# 02_-STM32F373BluePill.net
KiCad netlist of a schematic drawn in Altium Designer
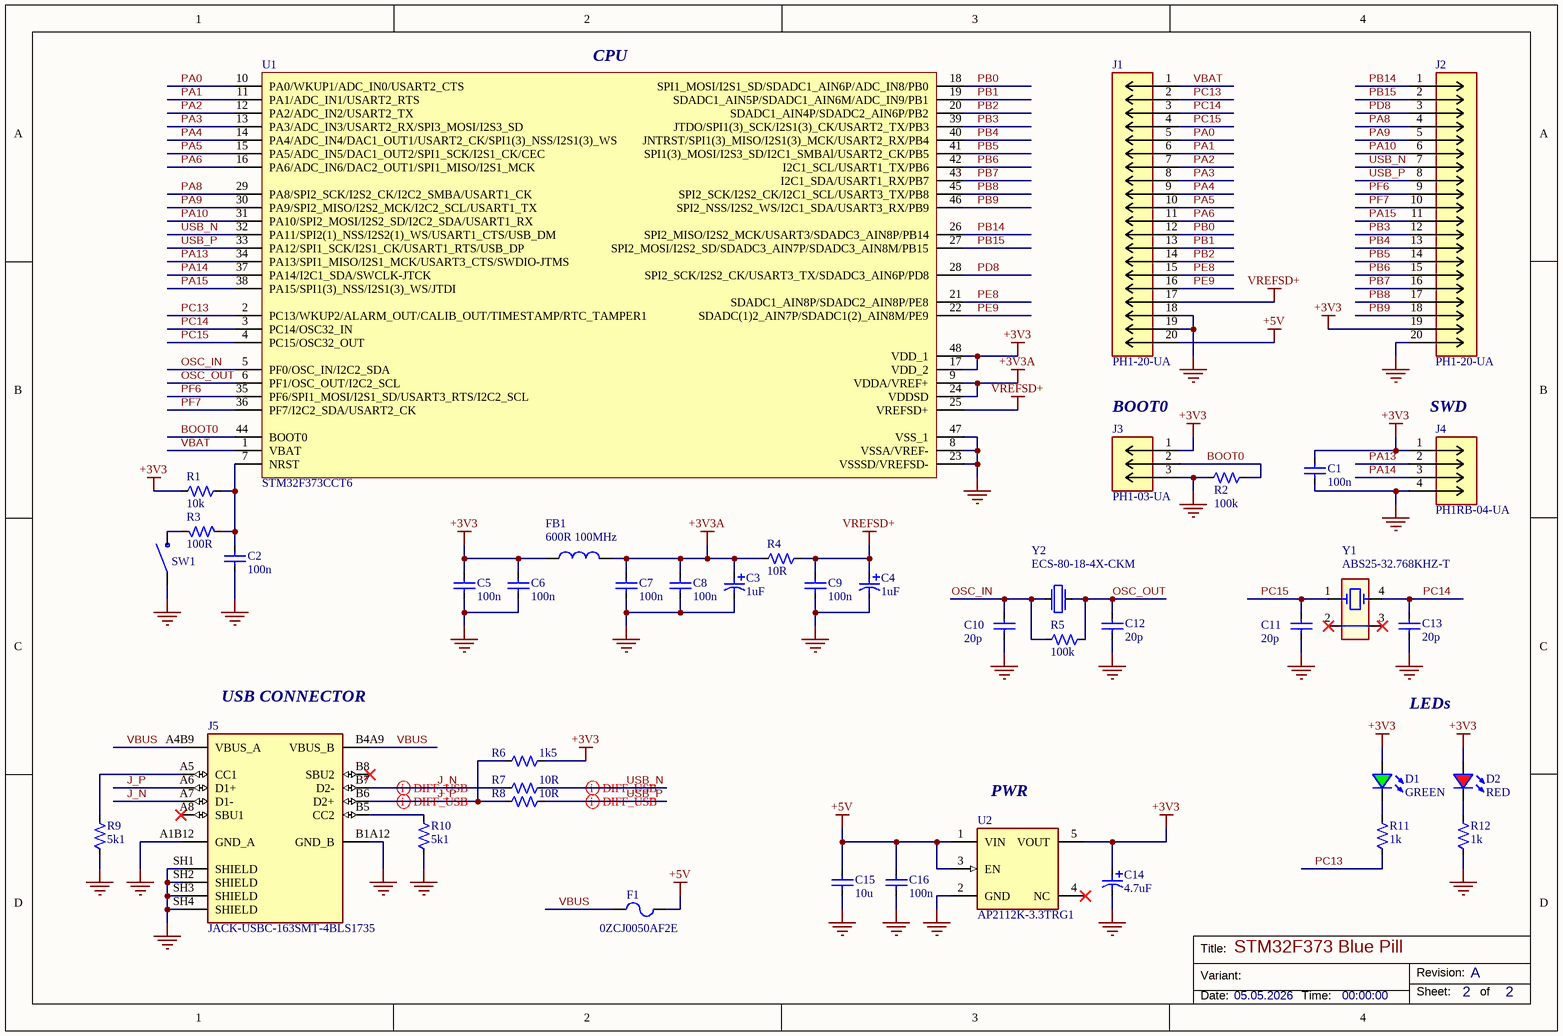
[diagram p0: [02]-STM32F373BluePill.SchDoc]

(export (version "E")
  (design (tool "Eeschema 10.0.6"))
  (components
    (comp (ref "C1")
      (value "100n")
      (footprint "CAPC0603(1608Metric)L")
      (description "0.1 µF ±10% 50V Ceramic Capacitor X7R 0603 (1608 Metric)")
      (fields (field (name "TOLERANCE") "10%"))
      (libsource (lib "STM32F373BluePill") (part "CAPC_GCM188R71H104KA57J"))
    )
    (comp (ref "C2")
      (value "100n")
      (footprint "CAPC0603(1608Metric)L")
      (description "0.1 µF ±10% 50V Ceramic Capacitor X7R 0603 (1608 Metric)")
      (fields (field (name "TOLERANCE") "10%"))
      (libsource (lib "STM32F373BluePill") (part "CAPC_GCM188R71H104KA57J"))
    )
    (comp (ref "C3")
      (value "1uF")
      (footprint "CAPMP3216X180N")
      (description "1 µF Molded Tantalum Capacitors 20 V 1206 (3216 Metric) 9Ohm")
      (fields (field (name "TOLERANCE") "10%") (field (name "VOLTAGE") "20V"))
      (libsource (lib "STM32F373BluePill") (part "CAP_T491A105K020AT"))
    )
    (comp (ref "C4")
      (value "1uF")
      (footprint "CAPMP3216X180N")
      (description "1 µF Molded Tantalum Capacitors 20 V 1206 (3216 Metric) 9Ohm")
      (fields (field (name "TOLERANCE") "10%") (field (name "VOLTAGE") "20V"))
      (libsource (lib "STM32F373BluePill") (part "CAP_T491A105K020AT"))
    )
    (comp (ref "C5")
      (value "100n")
      (footprint "CAPC0603(1608Metric)L")
      (description "0.1 µF ±10% 50V Ceramic Capacitor X7R 0603 (1608 Metric)")
      (fields (field (name "TOLERANCE") "10%"))
      (libsource (lib "STM32F373BluePill") (part "CAPC_GCM188R71H104KA57J"))
    )
    (comp (ref "C6")
      (value "100n")
      (footprint "CAPC0603(1608Metric)L")
      (description "0.1 µF ±10% 50V Ceramic Capacitor X7R 0603 (1608 Metric)")
      (fields (field (name "TOLERANCE") "10%"))
      (libsource (lib "STM32F373BluePill") (part "CAPC_GCM188R71H104KA57J"))
    )
    (comp (ref "C7")
      (value "100n")
      (footprint "CAPC0603(1608Metric)L")
      (description "0.1 µF ±10% 50V Ceramic Capacitor X7R 0603 (1608 Metric)")
      (fields (field (name "TOLERANCE") "10%"))
      (libsource (lib "STM32F373BluePill") (part "CAPC_GCM188R71H104KA57J"))
    )
    (comp (ref "C8")
      (value "100n")
      (footprint "CAPC0603(1608Metric)L")
      (description "0.1 µF ±10% 50V Ceramic Capacitor X7R 0603 (1608 Metric)")
      (fields (field (name "TOLERANCE") "10%"))
      (libsource (lib "STM32F373BluePill") (part "CAPC_GCM188R71H104KA57J"))
    )
    (comp (ref "C9")
      (value "100n")
      (footprint "CAPC0603(1608Metric)L")
      (description "0.1 µF ±10% 50V Ceramic Capacitor X7R 0603 (1608 Metric)")
      (fields (field (name "TOLERANCE") "10%"))
      (libsource (lib "STM32F373BluePill") (part "CAPC_GCM188R71H104KA57J"))
    )
    (comp (ref "C10")
      (value "20p")
      (footprint "CAPC0603(1608Metric)L")
      (description "20pF 100V C0G ±5% 0603 Multilayer Ceramic Capacitors MLCC - SMD/SMT ROHS")
      (fields (field (name "TOLERANCE") "5%"))
      (libsource (lib "STM32F373BluePill") (part "CAPC_GCM1885C2A200JA16D"))
    )
    (comp (ref "C11")
      (value "20p")
      (footprint "CAPC0603(1608Metric)L")
      (description "20pF 100V C0G ±5% 0603 Multilayer Ceramic Capacitors MLCC - SMD/SMT ROHS")
      (fields (field (name "TOLERANCE") "5%"))
      (libsource (lib "STM32F373BluePill") (part "CAPC_GCM1885C2A200JA16D"))
    )
    (comp (ref "C12")
      (value "20p")
      (footprint "CAPC0603(1608Metric)L")
      (description "20pF 100V C0G ±5% 0603 Multilayer Ceramic Capacitors MLCC - SMD/SMT ROHS")
      (fields (field (name "TOLERANCE") "5%"))
      (libsource (lib "STM32F373BluePill") (part "CAPC_GCM1885C2A200JA16D"))
    )
    (comp (ref "C13")
      (value "20p")
      (footprint "CAPC0603(1608Metric)L")
      (description "20pF 100V C0G ±5% 0603 Multilayer Ceramic Capacitors MLCC - SMD/SMT ROHS")
      (fields (field (name "TOLERANCE") "5%"))
      (libsource (lib "STM32F373BluePill") (part "CAPC_GCM1885C2A200JA16D"))
    )
    (comp (ref "C14")
      (value "4.7uF")
      (footprint "CAPMP3216X180N")
      (description "4.7 µF Molded Tantalum Capacitors 25 V 1206 (3216 Metric) 6Ohm")
      (fields (field (name "TOLERANCE") "10%"))
      (libsource (lib "STM32F373BluePill") (part "CAP_T491A475K025AT"))
    )
    (comp (ref "C15")
      (value "10u")
      (footprint "CAPC0603(1608Metric)L")
      (description "10 µF ±20% 16V Ceramic Capacitor X6S 0603 (1608 Metric)")
      (fields (field (name "TOLERANCE") "20%") (field (name "VOLTAGE") "16V"))
      (libsource (lib "STM32F373BluePill") (part "CAPC_GRM188C81C106MA73D"))
    )
    (comp (ref "C16")
      (value "100n")
      (footprint "CAPC0603(1608Metric)L")
      (description "0.1 µF ±10% 50V Ceramic Capacitor X7R 0603 (1608 Metric)")
      (fields (field (name "TOLERANCE") "10%"))
      (libsource (lib "STM32F373BluePill") (part "CAPC_GCM188R71H104KA57J"))
    )
    (comp (ref "D1")
      (value "GREEN")
      (footprint "WL-SMCW_0603_150060xx75003")
      (description "Led, Bright Green, 100Mcd, 572Nm Rohs Compliant: Yes")
      (libsource (lib "STM32F373BluePill") (part "LED_150060VS75003"))
    )
    (comp (ref "D2")
      (value "RED")
      (footprint "WL-SMCW_0603_150060xx75003")
      (description "LED RED CLEAR 0603 SMD")
      (libsource (lib "STM32F373BluePill") (part "LED_150060RS75003"))
    )
    (comp (ref "F1")
      (value "0ZCJ0050AF2E")
      (footprint "0ZCJ_BEL")
      (description "Resettable Fuse, PPTC, 1206 (3216 Metric), 0ZCJ Series, 24 VDC, 500 mA, 1 A, 0.1 s")
      (libsource (lib "STLinkV2_1") (part "0ZCJ0050AF2E"))
    )
    (comp (ref "FB1")
      (value "600R 100MHz")
      (footprint "BEADC1608X95N")
      (description "600 Ohms @ 100 MHz 1 Ferrite Bead 0603 (1608 Metric) 500mA 380mOhm")
      (fields (field (name "TOLERANCE") "25%"))
      (libsource (lib "STM32F373BluePill") (part "BLM18AG601SN1D"))
    )
    (comp (ref "J1")
      (value "PH1-20-UA")
      (footprint "CONN_PH1-20-UA_ADM")
      (description "Conn Unshrouded Header HDR 10 POS 2.54mm Solder RA Side Entry Thru-Hole Bag")
      (libsource (lib "STM32F373BluePill") (part "CON_PH1-20-UA"))
    )
    (comp (ref "J2")
      (value "PH1-20-UA")
      (footprint "CONN_PH1-20-UA_ADM")
      (description "Conn Unshrouded Header HDR 10 POS 2.54mm Solder RA Side Entry Thru-Hole Bag")
      (libsource (lib "STM32F373BluePill") (part "CON_PH1-20-UA"))
    )
    (comp (ref "J3")
      (value "PH1-03-UA")
      (footprint "CONN_PH1-03-UA")
      (description "Conn Unshrouded Header HDR 3 POS 2.54mm Solder ST Top Entry Thru-Hole Bag")
      (libsource (lib "STM32F373BluePill") (part "CON_PH1-03-UA"))
    )
    (comp (ref "J4")
      (value "PH1RB-04-UA")
      (footprint "CONN_PH1RB-04-UA")
      (description "PH1RB ROHS3Compliant COMMERCIAL UL CSA Connector Header 20mOhm -40C~105C 3A 250VAC")
      (libsource (lib "STM32F373BluePill") (part "CON_PH1RB-04-UA"))
    )
    (comp (ref "J5")
      (value "JACK-USBC-163SMT-4BLS1735")
      (footprint "JACK-USBC-163SMT-4BLS1735")
      (description "Usb Type C Jack IPX7 SMT")
      (libsource (lib "STLinkV2_1") (part "JACK-USBC-163SMT-4BLS1735"))
    )
    (comp (ref "R1")
      (value "10k")
      (footprint "RESC0603(1608Metric)L")
      (fields (field (name "TOLERANCE") "1%"))
      (libsource (lib "STM32F373BluePill") (part "RESC_AC0603FR-0710KL"))
    )
    (comp (ref "R2")
      (value "100k")
      (footprint "RESC0603(1608Metric)L")
      (description "100 kOhms ±0.5% 0.1W, 1/10W Chip Resistor 0603 (1608 Metric) Moisture Resistant Thick Film")
      (fields (field (name "TOLERANCE") "0.5%"))
      (libsource (lib "STM32F373BluePill") (part "RESC_RC0603DR-07100KL"))
    )
    (comp (ref "R3")
      (value "100R")
      (footprint "RESC0603(1608Metric)L")
      (description "100 Ohms ±1% 0.1W, 1/10W Chip Resistor 0603 (1608 Metric) Moisture Resistant Thick Film")
      (fields (field (name "TOLERANCE") "1%"))
      (libsource (lib "STM32F373BluePill") (part "RESC_RC0603FR-10100RL"))
    )
    (comp (ref "R4")
      (value "10R")
      (footprint "RESC0603(1608Metric)L")
      (description "Res Thick Film 0603 10 Ohm 1% 0.1W(1/10W) ±200ppm/C Pad SMD T/R")
      (fields (field (name "TOLERANCE") "1%"))
      (libsource (lib "STM32F373BluePill") (part "RESC_RC0603FR-0710RL"))
    )
    (comp (ref "R5")
      (value "100k")
      (footprint "RESC0603(1608Metric)L")
      (description "100 kOhms ±0.5% 0.1W, 1/10W Chip Resistor 0603 (1608 Metric) Moisture Resistant Thick Film")
      (fields (field (name "TOLERANCE") "0.5%"))
      (libsource (lib "STM32F373BluePill") (part "RESC_RC0603DR-07100KL"))
    )
    (comp (ref "R6")
      (value "1k5")
      (footprint "RESC0603(1608Metric)L")
      (fields (field (name "TOLERANCE") "1%"))
      (libsource (lib "STM32F373BluePill") (part "RESC_AC0603FR-071K5L"))
    )
    (comp (ref "R7")
      (value "10R")
      (footprint "RESC0603(1608Metric)L")
      (description "Res Thick Film 0603 10 Ohm 1% 0.1W(1/10W) ±200ppm/C Pad SMD T/R")
      (fields (field (name "TOLERANCE") "1%"))
      (libsource (lib "STM32F373BluePill") (part "RESC_RC0603FR-0710RL"))
    )
    (comp (ref "R8")
      (value "10R")
      (footprint "RESC0603(1608Metric)L")
      (description "Res Thick Film 0603 10 Ohm 1% 0.1W(1/10W) ±200ppm/C Pad SMD T/R")
      (fields (field (name "TOLERANCE") "1%"))
      (libsource (lib "STM32F373BluePill") (part "RESC_RC0603FR-0710RL"))
    )
    (comp (ref "R9")
      (value "5k1")
      (footprint "RESC0603(1608Metric)L")
      (description "5.1 kOhms ±1% 0.1W, 1/10W Chip Resistor 0603 (1608 Metric) Moisture Resistant Thick Film")
      (fields (field (name "TOLERANCE") "1%"))
      (libsource (lib "STM32F373BluePill") (part "RESC_RC0603FR-075K1L"))
    )
    (comp (ref "R10")
      (value "5k1")
      (footprint "RESC0603(1608Metric)L")
      (description "5.1 kOhms ±1% 0.1W, 1/10W Chip Resistor 0603 (1608 Metric) Moisture Resistant Thick Film")
      (fields (field (name "TOLERANCE") "1%"))
      (libsource (lib "STM32F373BluePill") (part "RESC_RC0603FR-075K1L"))
    )
    (comp (ref "R11")
      (value "1k")
      (footprint "RESC0603(1608Metric)L")
      (description "1 kOhms ±1% 0.1W, 1/10W Chip Resistor 0603 (1608 Metric) Moisture Resistant Thick Film")
      (fields (field (name "TOLERANCE") "1%"))
      (libsource (lib "STM32F373BluePill") (part "RESC_RC0603FR-101KL"))
    )
    (comp (ref "R12")
      (value "1k")
      (footprint "RESC0603(1608Metric)L")
      (description "1 kOhms ±1% 0.1W, 1/10W Chip Resistor 0603 (1608 Metric) Moisture Resistant Thick Film")
      (fields (field (name "TOLERANCE") "1%"))
      (libsource (lib "STM32F373BluePill") (part "RESC_RC0603FR-101KL"))
    )
    (comp (ref "SW1")
      (value "TS09-63-25-R-260-SMT-TR")
      (footprint "SW_TS09-63-25-R-260-SMT-TR")
      (description "Switch Tactile OFF (ON) SPST Rectangular Button Gull Wing 0.05A 12VDC 40000Cycles 2.6N SMD T/R")
      (libsource (lib "STM32F373BluePill") (part "SW_TS09-63-25-R-260-SMT-TR"))
    )
    (comp (ref "U1")
      (value "STM32F373CCT6")
      (footprint "QFP50P900X900X160-48N")
      (description "MCU, 32BIT, CORTEX-M4F, 72MHZ, LQFP-48")
      (fields (field (name "MANUFACTURER") "STMicroelectronics"))
      (libsource (lib "STM32F373BluePill") (part "IC_STM32F373CCT6"))
    )
    (comp (ref "U2")
      (value "AP2112K-3.3TRG1")
      (footprint "SOT95P285X140-5N")
      (description "AP2112 Series 0.6 A 3.3 V Fixed Output SMT LDO Linear Regulator - SOT23-5")
      (libsource (lib "STLinkV2_1") (part "AP2112K-3.3TRG1"))
    )
    (comp (ref "Y1")
      (value "ABS25-32.768KHZ-T")
      (footprint "XTAL_ABS25-32.768KHZ-6-1-T")
      (description "Crystal, Plastic Molded 32.768Khz, 12.5F, 20Ppm-40+85C, 8 X 4 X 2.5 Rohs Compliant: Yes")
      (fields (field (name "TOLERANCE") "0.002%"))
      (libsource (lib "STM32F373BluePill") (part "Y_ABS25-32.768KHZ-T"))
    )
    (comp (ref "Y2")
      (value "ECS-80-18-4X-CKM")
      (footprint "XTAL_ECS-80-18-4X-CKM")
      (description "8 MHz ±10ppm Crystal 18pF 80 Ohms HC-49/US")
      (libsource (lib "STM32F373BluePill") (part "Y_ECS-80-18-4X-CKM"))
    )
  )
  (nets
    (net (code "1") (name "+3V3") (class "Default")
      (node (ref "C1") (pin "2") (pinfunction "2_2") (pintype "passive"))
      (node (ref "C14") (pin "1") (pinfunction "1_1") (pintype "passive"))
      (node (ref "C5") (pin "2") (pinfunction "2_2") (pintype "passive"))
      (node (ref "C6") (pin "2") (pinfunction "2_2") (pintype "passive"))
      (node (ref "D1") (pin "1") (pinfunction "POS_1") (pintype "passive"))
      (node (ref "D2") (pin "1") (pinfunction "POS_1") (pintype "passive"))
      (node (ref "FB1") (pin "1") (pinfunction "1_1") (pintype "passive"))
      (node (ref "J2") (pin "19") (pinfunction "19_19") (pintype "passive"))
      (node (ref "J3") (pin "1") (pinfunction "1_1") (pintype "passive"))
      (node (ref "J4") (pin "1") (pinfunction "1_1") (pintype "passive"))
      (node (ref "R1") (pin "2") (pinfunction "2_2") (pintype "passive"))
      (node (ref "R6") (pin "1") (pinfunction "1_1") (pintype "passive"))
      (node (ref "U1") (pin "17") (pinfunction "VDD_2_17") (pintype "passive"))
      (node (ref "U1") (pin "48") (pinfunction "VDD_1_48") (pintype "passive"))
      (node (ref "U2") (pin "5") (pinfunction "VOUT_5") (pintype "power_in"))
    )
    (net (code "2") (name "+3V3A") (class "Default")
      (node (ref "C3") (pin "1") (pinfunction "1_1") (pintype "passive"))
      (node (ref "C7") (pin "2") (pinfunction "2_2") (pintype "passive"))
      (node (ref "C8") (pin "2") (pinfunction "2_2") (pintype "passive"))
      (node (ref "FB1") (pin "2") (pinfunction "2_2") (pintype "passive"))
      (node (ref "R4") (pin "2") (pinfunction "2_2") (pintype "passive"))
      (node (ref "U1") (pin "24") (pinfunction "VDDSD_24") (pintype "passive"))
      (node (ref "U1") (pin "9") (pinfunction "VDDA/VREF+_9") (pintype "passive"))
    )
    (net (code "3") (name "+5V") (class "Default")
      (node (ref "C15") (pin "2") (pinfunction "2_2") (pintype "passive"))
      (node (ref "C16") (pin "2") (pinfunction "2_2") (pintype "passive"))
      (node (ref "F1") (pin "2") (pinfunction "2_2") (pintype "passive"))
      (node (ref "J1") (pin "20") (pinfunction "20_20") (pintype "passive"))
      (node (ref "U2") (pin "1") (pinfunction "VIN_1") (pintype "power_in"))
      (node (ref "U2") (pin "3") (pinfunction "EN_3") (pintype "input"))
    )
    (net (code "4") (name "/BOOT0") (class "Default")
      (node (ref "J3") (pin "2") (pinfunction "2_2") (pintype "passive"))
      (node (ref "R2") (pin "1") (pinfunction "1_1") (pintype "passive"))
      (node (ref "U1") (pin "44") (pinfunction "BOOT0_44") (pintype "passive"))
    )
    (net (code "5") (name "/J_N") (class "Default")
      (node (ref "J5") (pin "A7") (pinfunction "D1-_A7") (pintype "bidirectional"))
      (node (ref "J5") (pin "B7") (pinfunction "D2-_B7") (pintype "bidirectional"))
      (node (ref "R7") (pin "2") (pinfunction "2_2") (pintype "passive"))
    )
    (net (code "6") (name "/J_P") (class "Default")
      (node (ref "J5") (pin "A6") (pinfunction "D1+_A6") (pintype "bidirectional"))
      (node (ref "J5") (pin "B6") (pinfunction "D2+_B6") (pintype "bidirectional"))
      (node (ref "R6") (pin "2") (pinfunction "2_2") (pintype "passive"))
      (node (ref "R8") (pin "2") (pinfunction "2_2") (pintype "passive"))
    )
    (net (code "7") (name "/OSC_IN") (class "Default")
      (node (ref "C10") (pin "2") (pinfunction "2_2") (pintype "passive"))
      (node (ref "R5") (pin "2") (pinfunction "2_2") (pintype "passive"))
      (node (ref "U1") (pin "5") (pinfunction "PF0/OSC_IN/I2C2_SDA_5") (pintype "passive"))
      (node (ref "Y2") (pin "1") (pintype "passive"))
    )
    (net (code "8") (name "/OSC_OUT") (class "Default")
      (node (ref "C12") (pin "2") (pinfunction "2_2") (pintype "passive"))
      (node (ref "R5") (pin "1") (pinfunction "1_1") (pintype "passive"))
      (node (ref "U1") (pin "6") (pinfunction "PF1/OSC_OUT/I2C2_SCL_6") (pintype "passive"))
      (node (ref "Y2") (pin "2") (pintype "passive"))
    )
    (net (code "9") (name "/PA0") (class "Default")
      (node (ref "J1") (pin "5") (pinfunction "5_5") (pintype "passive"))
      (node (ref "U1") (pin "10") (pinfunction "PA0/WKUP1/ADC_IN0/USART2_CTS_10") (pintype "passive"))
    )
    (net (code "10") (name "/PA1") (class "Default")
      (node (ref "J1") (pin "6") (pinfunction "6_6") (pintype "passive"))
      (node (ref "U1") (pin "11") (pinfunction "PA1/ADC_IN1/USART2_RTS_11") (pintype "passive"))
    )
    (net (code "11") (name "/PA2") (class "Default")
      (node (ref "J1") (pin "7") (pinfunction "7_7") (pintype "passive"))
      (node (ref "U1") (pin "12") (pinfunction "PA2/ADC_IN2/USART2_TX_12") (pintype "passive"))
    )
    (net (code "12") (name "/PA3") (class "Default")
      (node (ref "J1") (pin "8") (pinfunction "8_8") (pintype "passive"))
      (node (ref "U1") (pin "13") (pinfunction "PA3/ADC_IN3/USART2_RX/SPI3_MOSI/I2S3_SD_13") (pintype "passive"))
    )
    (net (code "13") (name "/PA4") (class "Default")
      (node (ref "J1") (pin "9") (pinfunction "9_9") (pintype "passive"))
      (node (ref "U1") (pin "14") (pinfunction "PA4/ADC_IN4/DAC1_OUT1/USART2_CK/SPI1(3)_NSS/I2S1(3)_WS_14") (pintype "passive"))
    )
    (net (code "14") (name "/PA5") (class "Default")
      (node (ref "J1") (pin "10") (pinfunction "10_10") (pintype "passive"))
      (node (ref "U1") (pin "15") (pinfunction "PA5/ADC_IN5/DAC1_OUT2/SPI1_SCK/I2S1_CK/CEC_15") (pintype "passive"))
    )
    (net (code "15") (name "/PA6") (class "Default")
      (node (ref "J1") (pin "11") (pinfunction "11_11") (pintype "passive"))
      (node (ref "U1") (pin "16") (pinfunction "PA6/ADC_IN6/DAC2_OUT1/SPI1_MISO/I2S1_MCK_16") (pintype "passive"))
    )
    (net (code "16") (name "/PA8") (class "Default")
      (node (ref "J2") (pin "4") (pinfunction "4_4") (pintype "passive"))
      (node (ref "U1") (pin "29") (pinfunction "PA8/SPI2_SCK/I2S2_CK/I2C2_SMBA/USART1_CK_29") (pintype "passive"))
    )
    (net (code "17") (name "/PA9") (class "Default")
      (node (ref "J2") (pin "5") (pinfunction "5_5") (pintype "passive"))
      (node (ref "U1") (pin "30") (pinfunction "PA9/SPI2_MISO/I2S2_MCK/I2C2_SCL/USART1_TX_30") (pintype "passive"))
    )
    (net (code "18") (name "/PA10") (class "Default")
      (node (ref "J2") (pin "6") (pinfunction "6_6") (pintype "passive"))
      (node (ref "U1") (pin "31") (pinfunction "PA10/SPI2_MOSI/I2S2_SD/I2C2_SDA/USART1_RX_31") (pintype "passive"))
    )
    (net (code "19") (name "/PA13") (class "Default")
      (node (ref "J4") (pin "2") (pinfunction "2_2") (pintype "passive"))
      (node (ref "U1") (pin "34") (pinfunction "PA13/SPI1_MISO/I2S1_MCK/USART3_CTS/SWDIO-JTMS_34") (pintype "passive"))
    )
    (net (code "20") (name "/PA14") (class "Default")
      (node (ref "J4") (pin "3") (pinfunction "3_3") (pintype "passive"))
      (node (ref "U1") (pin "37") (pinfunction "PA14/I2C1_SDA/SWCLK-JTCK_37") (pintype "passive"))
    )
    (net (code "21") (name "/PA15") (class "Default")
      (node (ref "J2") (pin "11") (pinfunction "11_11") (pintype "passive"))
      (node (ref "U1") (pin "38") (pinfunction "PA15/SPI1(3)_NSS/I2S1(3)_WS/JTDI_38") (pintype "passive"))
    )
    (net (code "22") (name "/PB0") (class "Default")
      (node (ref "J1") (pin "12") (pinfunction "12_12") (pintype "passive"))
      (node (ref "U1") (pin "18") (pinfunction "SPI1_MOSI/I2S1_SD/SDADC1_AIN6P/ADC_IN8/PB0_18") (pintype "passive"))
    )
    (net (code "23") (name "/PB1") (class "Default")
      (node (ref "J1") (pin "13") (pinfunction "13_13") (pintype "passive"))
      (node (ref "U1") (pin "19") (pinfunction "SDADC1_AIN5P/SDADC1_AIN6M/ADC_IN9/PB1_19") (pintype "passive"))
    )
    (net (code "24") (name "/PB2") (class "Default")
      (node (ref "J1") (pin "14") (pinfunction "14_14") (pintype "passive"))
      (node (ref "U1") (pin "20") (pinfunction "SDADC1_AIN4P/SDADC2_AIN6P/PB2_20") (pintype "passive"))
    )
    (net (code "25") (name "/PB3") (class "Default")
      (node (ref "J2") (pin "12") (pinfunction "12_12") (pintype "passive"))
      (node (ref "U1") (pin "39") (pinfunction "JTDO/SPI1(3)_SCK/I2S1(3)_CK/USART2_TX/PB3_39") (pintype "passive"))
    )
    (net (code "26") (name "/PB4") (class "Default")
      (node (ref "J2") (pin "13") (pinfunction "13_13") (pintype "passive"))
      (node (ref "U1") (pin "40") (pinfunction "JNTRST/SPI1(3)_MISO/I2S1(3)_MCK/USART2_RX/PB4_40") (pintype "passive"))
    )
    (net (code "27") (name "/PB5") (class "Default")
      (node (ref "J2") (pin "14") (pinfunction "14_14") (pintype "passive"))
      (node (ref "U1") (pin "41") (pinfunction "SPI1(3)_MOSI/I2S3_SD/I2C1_SMBAl/USART2_CK/PB5_41") (pintype "passive"))
    )
    (net (code "28") (name "/PB6") (class "Default")
      (node (ref "J2") (pin "15") (pinfunction "15_15") (pintype "passive"))
      (node (ref "U1") (pin "42") (pinfunction "I2C1_SCL/USART1_TX/PB6_42") (pintype "passive"))
    )
    (net (code "29") (name "/PB7") (class "Default")
      (node (ref "J2") (pin "16") (pinfunction "16_16") (pintype "passive"))
      (node (ref "U1") (pin "43") (pinfunction "I2C1_SDA/USART1_RX/PB7_43") (pintype "passive"))
    )
    (net (code "30") (name "/PB8") (class "Default")
      (node (ref "J2") (pin "17") (pinfunction "17_17") (pintype "passive"))
      (node (ref "U1") (pin "45") (pinfunction "SPI2_SCK/I2S2_CK/I2C1_SCL/USART3_TX/PB8_45") (pintype "passive"))
    )
    (net (code "31") (name "/PB9") (class "Default")
      (node (ref "J2") (pin "18") (pinfunction "18_18") (pintype "passive"))
      (node (ref "U1") (pin "46") (pinfunction "SPI2_NSS/I2S2_WS/I2C1_SDA/USART3_RX/PB9_46") (pintype "passive"))
    )
    (net (code "32") (name "/PB14") (class "Default")
      (node (ref "J2") (pin "1") (pinfunction "1_1") (pintype "passive"))
      (node (ref "U1") (pin "26") (pinfunction "SPI2_MISO/I2S2_MCK/USART3/SDADC3_AIN8P/PB14_26") (pintype "passive"))
    )
    (net (code "33") (name "/PB15") (class "Default")
      (node (ref "J2") (pin "2") (pinfunction "2_2") (pintype "passive"))
      (node (ref "U1") (pin "27") (pinfunction "SPI2_MOSI/I2S2_SD/SDADC3_AIN7P/SDADC3_AIN8M/PB15_27") (pintype "passive"))
    )
    (net (code "34") (name "/PC13") (class "Default")
      (node (ref "J1") (pin "2") (pinfunction "2_2") (pintype "passive"))
      (node (ref "R11") (pin "2") (pinfunction "2_2") (pintype "passive"))
      (node (ref "U1") (pin "2") (pinfunction "PC13/WKUP2/ALARM_OUT/CALIB_OUT/TIMESTAMP/RTC_TAMPER1_2") (pintype "passive"))
    )
    (net (code "35") (name "/PC14") (class "Default")
      (node (ref "C13") (pin "2") (pinfunction "2_2") (pintype "passive"))
      (node (ref "J1") (pin "3") (pinfunction "3_3") (pintype "passive"))
      (node (ref "U1") (pin "3") (pinfunction "PC14/OSC32_IN_3") (pintype "passive"))
      (node (ref "Y1") (pin "4") (pinfunction "4_4") (pintype "passive"))
    )
    (net (code "36") (name "/PC15") (class "Default")
      (node (ref "C11") (pin "2") (pinfunction "2_2") (pintype "passive"))
      (node (ref "J1") (pin "4") (pinfunction "4_4") (pintype "passive"))
      (node (ref "U1") (pin "4") (pinfunction "PC15/OSC32_OUT_4") (pintype "passive"))
      (node (ref "Y1") (pin "1") (pinfunction "1_1") (pintype "passive"))
    )
    (net (code "37") (name "/PD8") (class "Default")
      (node (ref "J2") (pin "3") (pinfunction "3_3") (pintype "passive"))
      (node (ref "U1") (pin "28") (pinfunction "SPI2_SCK/I2S2_CK/USART3_TX/SDADC3_AIN6P/PD8_28") (pintype "passive"))
    )
    (net (code "38") (name "/PE8") (class "Default")
      (node (ref "J1") (pin "15") (pinfunction "15_15") (pintype "passive"))
      (node (ref "U1") (pin "21") (pinfunction "SDADC1_AIN8P/SDADC2_AIN8P/PE8_21") (pintype "passive"))
    )
    (net (code "39") (name "/PE9") (class "Default")
      (node (ref "J1") (pin "16") (pinfunction "16_16") (pintype "passive"))
      (node (ref "U1") (pin "22") (pinfunction "SDADC(1)2_AIN7P/SDADC1(2)_AIN8M/PE9_22") (pintype "passive"))
    )
    (net (code "40") (name "/PF6") (class "Default")
      (node (ref "J2") (pin "9") (pinfunction "9_9") (pintype "passive"))
      (node (ref "U1") (pin "35") (pinfunction "PF6/SPI1_MOSI/I2S1_SD/USART3_RTS/I2C2_SCL_35") (pintype "passive"))
    )
    (net (code "41") (name "/PF7") (class "Default")
      (node (ref "J2") (pin "10") (pinfunction "10_10") (pintype "passive"))
      (node (ref "U1") (pin "36") (pinfunction "PF7/I2C2_SDA/USART2_CK_36") (pintype "passive"))
    )
    (net (code "42") (name "/USB_N") (class "Default")
      (node (ref "J2") (pin "7") (pinfunction "7_7") (pintype "passive"))
      (node (ref "R7") (pin "1") (pinfunction "1_1") (pintype "passive"))
      (node (ref "U1") (pin "32") (pinfunction "PA11/SPI2(1)_NSS/I2S2(1)_WS/USART1_CTS/USB_DM_32") (pintype "passive"))
    )
    (net (code "43") (name "/USB_P") (class "Default")
      (node (ref "J2") (pin "8") (pinfunction "8_8") (pintype "passive"))
      (node (ref "R8") (pin "1") (pinfunction "1_1") (pintype "passive"))
      (node (ref "U1") (pin "33") (pinfunction "PA12/SPI1_SCK/I2S1_CK/USART1_RTS/USB_DP_33") (pintype "passive"))
    )
    (net (code "44") (name "/VBAT") (class "Default")
      (node (ref "J1") (pin "1") (pinfunction "1_1") (pintype "passive"))
      (node (ref "U1") (pin "1") (pinfunction "VBAT_1") (pintype "passive"))
    )
    (net (code "45") (name "/VBUS") (class "Default")
      (node (ref "F1") (pin "1") (pinfunction "1_1") (pintype "passive"))
      (node (ref "J5") (pin "A4B9") (pinfunction "VBUS_A_A4B9") (pintype "power_in"))
      (node (ref "J5") (pin "B4A9") (pinfunction "VBUS_B_B4A9") (pintype "power_in"))
    )
    (net (code "46") (name "GND") (class "Default")
      (node (ref "C1") (pin "1") (pinfunction "1_1") (pintype "passive"))
      (node (ref "C10") (pin "1") (pinfunction "1_1") (pintype "passive"))
      (node (ref "C11") (pin "1") (pinfunction "1_1") (pintype "passive"))
      (node (ref "C12") (pin "1") (pinfunction "1_1") (pintype "passive"))
      (node (ref "C13") (pin "1") (pinfunction "1_1") (pintype "passive"))
      (node (ref "C14") (pin "2") (pinfunction "2_2") (pintype "passive"))
      (node (ref "C15") (pin "1") (pinfunction "1_1") (pintype "passive"))
      (node (ref "C16") (pin "1") (pinfunction "1_1") (pintype "passive"))
      (node (ref "C2") (pin "1") (pinfunction "1_1") (pintype "passive"))
      (node (ref "C3") (pin "2") (pinfunction "2_2") (pintype "passive"))
      (node (ref "C4") (pin "2") (pinfunction "2_2") (pintype "passive"))
      (node (ref "C5") (pin "1") (pinfunction "1_1") (pintype "passive"))
      (node (ref "C6") (pin "1") (pinfunction "1_1") (pintype "passive"))
      (node (ref "C7") (pin "1") (pinfunction "1_1") (pintype "passive"))
      (node (ref "C8") (pin "1") (pinfunction "1_1") (pintype "passive"))
      (node (ref "C9") (pin "1") (pinfunction "1_1") (pintype "passive"))
      (node (ref "J1") (pin "18") (pinfunction "18_18") (pintype "passive"))
      (node (ref "J1") (pin "19") (pinfunction "19_19") (pintype "passive"))
      (node (ref "J2") (pin "20") (pinfunction "20_20") (pintype "passive"))
      (node (ref "J3") (pin "3") (pinfunction "3_3") (pintype "passive"))
      (node (ref "J4") (pin "4") (pinfunction "4_4") (pintype "passive"))
      (node (ref "J5") (pin "A1B12") (pinfunction "GND_A_A1B12") (pintype "power_in"))
      (node (ref "J5") (pin "B1A12") (pinfunction "GND_B_B1A12") (pintype "power_in"))
      (node (ref "J5") (pin "SH1") (pinfunction "SHIELD_SH1") (pintype "passive"))
      (node (ref "J5") (pin "SH2") (pinfunction "SHIELD_SH2") (pintype "passive"))
      (node (ref "J5") (pin "SH3") (pinfunction "SHIELD_SH3") (pintype "passive"))
      (node (ref "J5") (pin "SH4") (pinfunction "SHIELD_SH4") (pintype "passive"))
      (node (ref "R10") (pin "2") (pinfunction "2_2") (pintype "passive"))
      (node (ref "R12") (pin "2") (pinfunction "2_2") (pintype "passive"))
      (node (ref "R2") (pin "2") (pinfunction "2_2") (pintype "passive"))
      (node (ref "R9") (pin "2") (pinfunction "2_2") (pintype "passive"))
      (node (ref "SW1") (pin "1") (pinfunction "1_1") (pintype "passive"))
      (node (ref "U1") (pin "23") (pinfunction "VSSSD/VREFSD-_23") (pintype "passive"))
      (node (ref "U1") (pin "47") (pinfunction "VSS_1_47") (pintype "passive"))
      (node (ref "U1") (pin "8") (pinfunction "VSSA/VREF-_8") (pintype "passive"))
      (node (ref "U2") (pin "2") (pinfunction "GND_2") (pintype "power_in"))
    )
    (net (code "47") (name "Net-(D1-NEG)") (class "Default")
      (node (ref "D1") (pin "2") (pinfunction "NEG_2") (pintype "passive"))
      (node (ref "R11") (pin "1") (pinfunction "1_1") (pintype "passive"))
    )
    (net (code "48") (name "Net-(D2-NEG)") (class "Default")
      (node (ref "D2") (pin "2") (pinfunction "NEG_2") (pintype "passive"))
      (node (ref "R12") (pin "1") (pinfunction "1_1") (pintype "passive"))
    )
    (net (code "49") (name "Net-(J5-CC1)") (class "Default")
      (node (ref "J5") (pin "A5") (pinfunction "CC1_A5") (pintype "bidirectional"))
      (node (ref "R9") (pin "1") (pinfunction "1_1") (pintype "passive"))
    )
    (net (code "50") (name "Net-(J5-CC2)") (class "Default")
      (node (ref "J5") (pin "B5") (pinfunction "CC2_B5") (pintype "bidirectional"))
      (node (ref "R10") (pin "1") (pinfunction "1_1") (pintype "passive"))
    )
    (net (code "51") (name "Net-(R3-Pad1)") (class "Default")
      (node (ref "R3") (pin "1") (pinfunction "1_1") (pintype "passive"))
      (node (ref "SW1") (pin "2") (pinfunction "2_2") (pintype "passive"))
    )
    (net (code "52") (name "Net-(U1-NRST)") (class "Default")
      (node (ref "C2") (pin "2") (pinfunction "2_2") (pintype "passive"))
      (node (ref "R1") (pin "1") (pinfunction "1_1") (pintype "passive"))
      (node (ref "R3") (pin "2") (pinfunction "2_2") (pintype "passive"))
      (node (ref "U1") (pin "7") (pinfunction "NRST_7") (pintype "passive"))
    )
    (net (code "53") (name "VREFSD+") (class "Default")
      (node (ref "C4") (pin "1") (pinfunction "1_1") (pintype "passive"))
      (node (ref "C9") (pin "2") (pinfunction "2_2") (pintype "passive"))
      (node (ref "J1") (pin "17") (pinfunction "17_17") (pintype "passive"))
      (node (ref "R4") (pin "1") (pinfunction "1_1") (pintype "passive"))
      (node (ref "U1") (pin "25") (pinfunction "VREFSD+_25") (pintype "passive"))
    )
    (net (code "54") (name "unconnected-(J5-SBU1-PadA8)") (class "Default")
      (node (ref "J5") (pin "A8") (pinfunction "SBU1_A8") (pintype "bidirectional+no_connect"))
    )
    (net (code "55") (name "unconnected-(J5-SBU2-PadB8)") (class "Default")
      (node (ref "J5") (pin "B8") (pinfunction "SBU2_B8") (pintype "bidirectional+no_connect"))
    )
    (net (code "56") (name "unconnected-(U2-NC-Pad4)") (class "Default")
      (node (ref "U2") (pin "4") (pinfunction "NC_4") (pintype "passive+no_connect"))
    )
    (net (code "57") (name "unconnected-(Y1-Pad2)") (class "Default")
      (node (ref "Y1") (pin "2") (pinfunction "2_2") (pintype "passive+no_connect"))
    )
    (net (code "58") (name "unconnected-(Y1-Pad3)") (class "Default")
      (node (ref "Y1") (pin "3") (pinfunction "3_3") (pintype "passive+no_connect"))
    )
  )
)
